# CALclock-r1.net
KiCad netlist of a schematic drawn in EAGLE
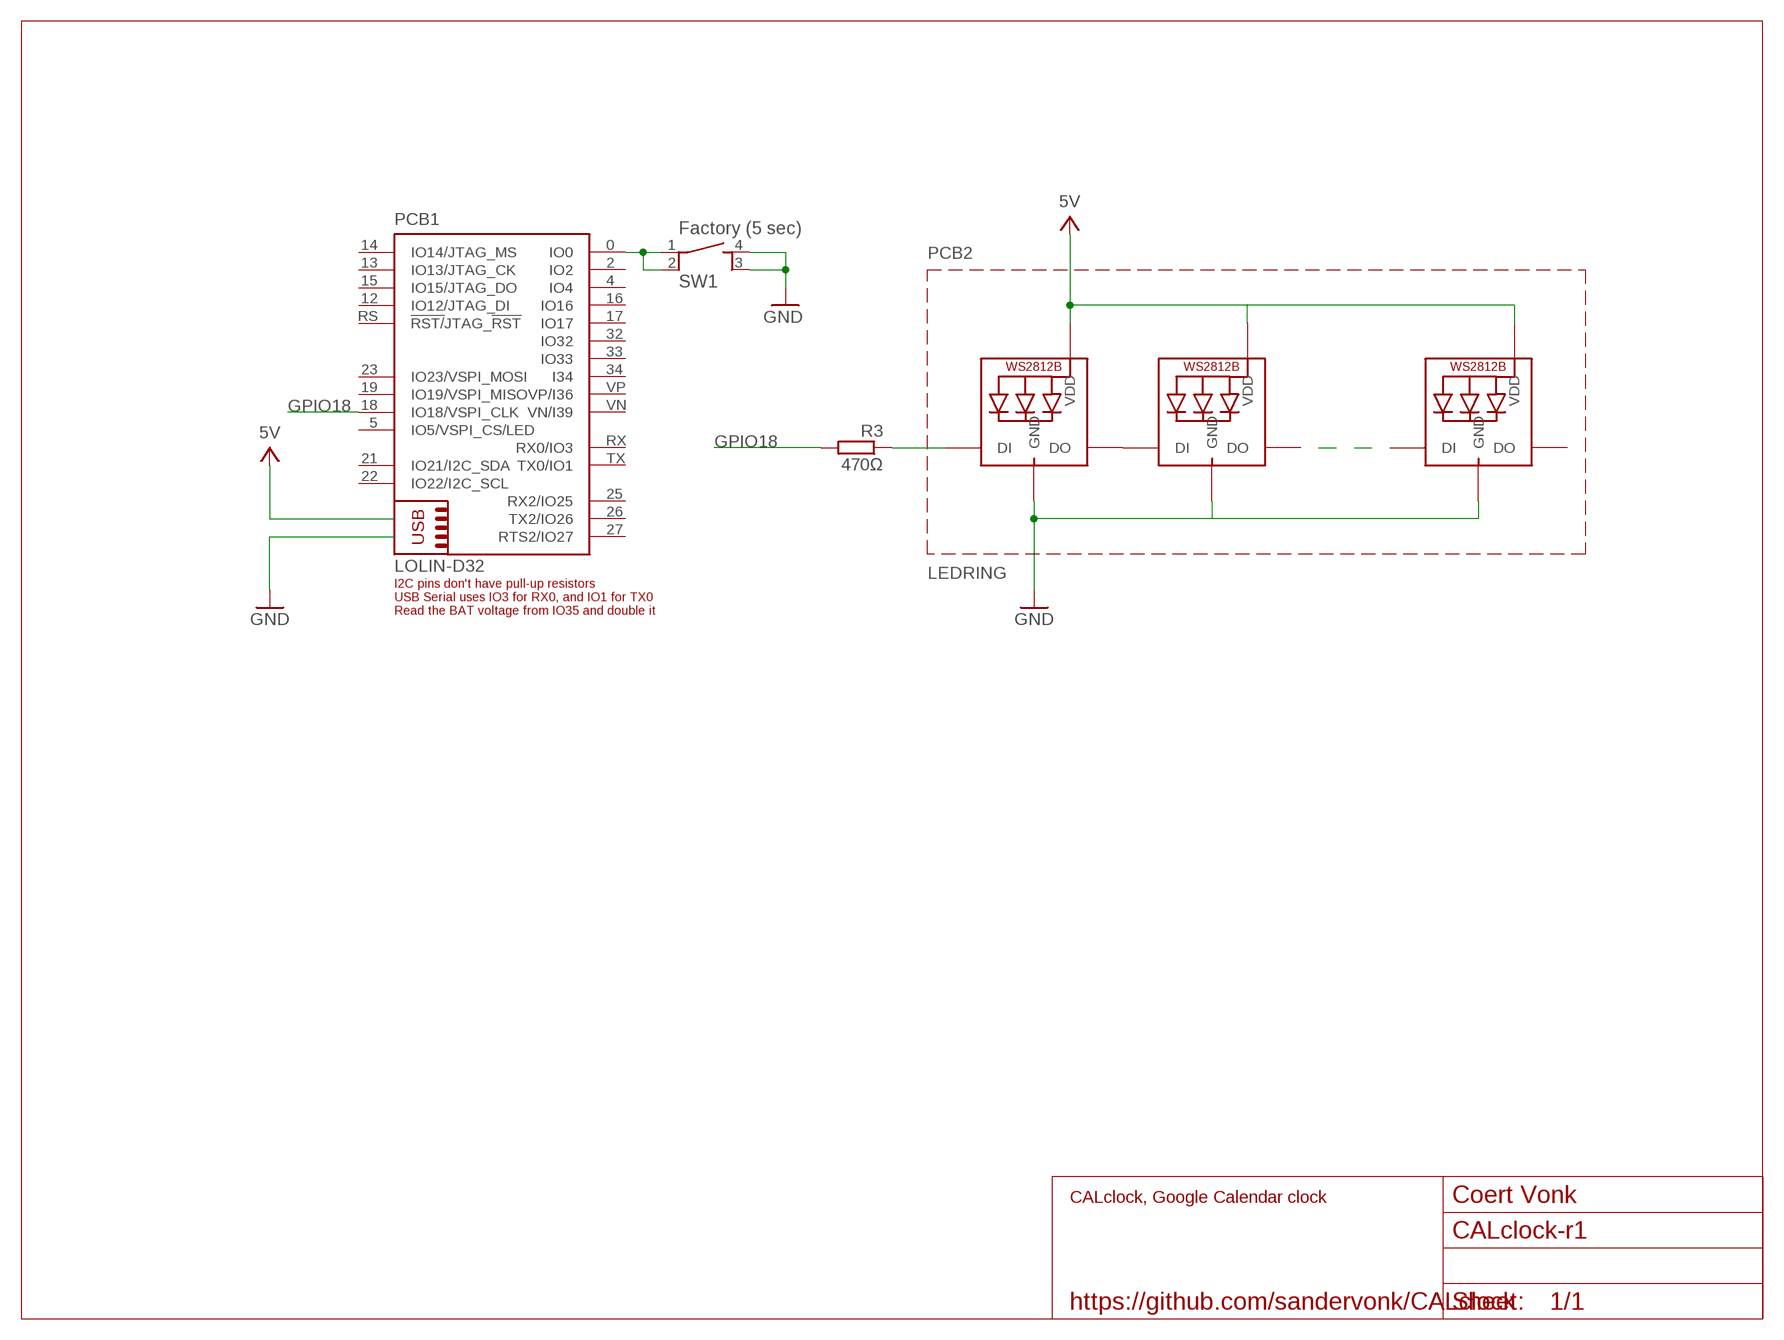
[diagram p0: schematic, sheet 1]

(export (version "E")
  (design (tool "Eeschema 10.0.6"))
  (components
    (comp (ref "LED1")
      (value "WS2812B5050")
      (footprint "eagle-import:WS2812B")
      (fields (field (name "MF") "Seeed Technology") (field (name "MP") "WS2812B"))
      (libsource (lib "eagle-import") (part "WS2812B5050"))
    )
    (comp (ref "LED2")
      (value "WS2812B5050")
      (footprint "eagle-import:WS2812B")
      (fields (field (name "MF") "Seeed Technology") (field (name "MP") "WS2812B"))
      (libsource (lib "eagle-import") (part "WS2812B5050"))
    )
    (comp (ref "LED3")
      (value "WS2812B5050")
      (footprint "eagle-import:WS2812B")
      (fields (field (name "MF") "Seeed Technology") (field (name "MP") "WS2812B"))
      (libsource (lib "eagle-import") (part "WS2812B5050"))
    )
    (comp (ref "PCB1")
      (value "LOLIN-D32")
      (footprint "eagle-import:LOLIN-D32")
      (fields (field (name "MANF") "WEMOS Electronics"))
      (libsource (lib "eagle-import") (part "LOLIN-D32"))
    )
    (comp (ref "R3")
      (value "470Ω")
      (footprint "eagle-import:R0805")
      (fields (field (name "MANF") "Bourns"))
      (libsource (lib "eagle-import") (part "R-EU_R0805"))
    )
    (comp (ref "SW1")
      (value "Factory (5 sec)")
      (footprint "eagle-import:TE_1-1825910-4")
      (fields
        (field (name "COMMENT") "1-1825910-4")
        (field (name "DIGI-KEY_PART_NUMBER") "450-1653-ND")
        (field (name "MF") "TE Connectivity")
      )
      (libsource (lib "eagle-import") (part "1-1825910-4"))
    )
  )
  (nets
    (net (code "1") (name "/GPIO18") (class "Default")
      (node (ref "PCB1") (pin "18") (pinfunction "IO18/VSPI_CLK_18") (pintype "bidirectional"))
      (node (ref "R3") (pin "2") (pinfunction "2_2") (pintype "passive"))
    )
    (net (code "2") (name "5V") (class "Default")
      (node (ref "LED1") (pin "1-VDD") (pinfunction "VDD_1-VDD") (pintype "power_in"))
      (node (ref "LED3") (pin "1-VDD") (pinfunction "VDD_1-VDD") (pintype "power_in"))
    )
    (net (code "3") (name "GND") (class "Default")
      (node (ref "LED1") (pin "3-GND") (pinfunction "GND_3-GND") (pintype "power_in"))
      (node (ref "LED3") (pin "3-GND") (pinfunction "GND_3-GND") (pintype "power_in"))
      (node (ref "SW1") (pin "3") (pinfunction "3_3") (pintype "passive"))
      (node (ref "SW1") (pin "4") (pinfunction "4_4") (pintype "passive"))
    )
    (net (code "4") (name "Net-(LED1-DI)") (class "Default")
      (node (ref "LED1") (pin "4-DIN") (pinfunction "DI_4-DIN") (pintype "input"))
      (node (ref "R3") (pin "1") (pinfunction "1_1") (pintype "passive"))
    )
    (net (code "5") (name "Net-(LED1-DO)") (class "Default")
      (node (ref "LED1") (pin "2-DOUT") (pinfunction "DO_2-DOUT") (pintype "output"))
      (node (ref "LED2") (pin "4-DIN") (pinfunction "DI_4-DIN") (pintype "input"))
    )
    (net (code "6") (name "Net-(PCB1A-IO0)") (class "Default")
      (node (ref "PCB1") (pin "0") (pinfunction "IO0_0") (pintype "bidirectional"))
      (node (ref "SW1") (pin "1") (pinfunction "1_1") (pintype "passive"))
      (node (ref "SW1") (pin "2") (pinfunction "2_2") (pintype "passive"))
    )
    (net (code "7") (name "unconnected-(LED2-DO-Pad2-DOUT)") (class "Default")
      (node (ref "LED2") (pin "2-DOUT") (pinfunction "DO_2-DOUT") (pintype "output"))
    )
    (net (code "8") (name "unconnected-(LED2-GND-Pad3-GND)") (class "Default")
      (node (ref "LED2") (pin "3-GND") (pinfunction "GND_3-GND") (pintype "power_in"))
    )
    (net (code "9") (name "unconnected-(LED2-VDD-Pad1-VDD)") (class "Default")
      (node (ref "LED2") (pin "1-VDD") (pinfunction "VDD_1-VDD") (pintype "power_in"))
    )
    (net (code "10") (name "unconnected-(LED3-DI-Pad4-DIN)") (class "Default")
      (node (ref "LED3") (pin "4-DIN") (pinfunction "DI_4-DIN") (pintype "input"))
    )
    (net (code "11") (name "unconnected-(LED3-DO-Pad2-DOUT)") (class "Default")
      (node (ref "LED3") (pin "2-DOUT") (pinfunction "DO_2-DOUT") (pintype "output"))
    )
    (net (code "12") (name "unconnected-(PCB1A-I34-Pad34)") (class "Default")
      (node (ref "PCB1") (pin "34") (pinfunction "I34_34") (pintype "input"))
    )
    (net (code "13") (name "unconnected-(PCB1A-IO2-Pad2)") (class "Default")
      (node (ref "PCB1") (pin "2") (pinfunction "IO2_2") (pintype "bidirectional"))
    )
    (net (code "14") (name "unconnected-(PCB1A-IO4-Pad4)") (class "Default")
      (node (ref "PCB1") (pin "4") (pinfunction "IO4_4") (pintype "bidirectional"))
    )
    (net (code "15") (name "unconnected-(PCB1A-IO5{slash}VSPI_CS{slash}LED-Pad5)") (class "Default")
      (node (ref "PCB1") (pin "5") (pinfunction "IO5/VSPI_CS/LED_5") (pintype "bidirectional"))
    )
    (net (code "16") (name "unconnected-(PCB1A-IO12{slash}JTAG_DI-Pad12)") (class "Default")
      (node (ref "PCB1") (pin "12") (pinfunction "IO12/JTAG_DI_12") (pintype "bidirectional"))
    )
    (net (code "17") (name "unconnected-(PCB1A-IO13{slash}JTAG_CK-Pad13)") (class "Default")
      (node (ref "PCB1") (pin "13") (pinfunction "IO13/JTAG_CK_13") (pintype "bidirectional"))
    )
    (net (code "18") (name "unconnected-(PCB1A-IO14{slash}JTAG_MS-Pad14)") (class "Default")
      (node (ref "PCB1") (pin "14") (pinfunction "IO14/JTAG_MS_14") (pintype "bidirectional"))
    )
    (net (code "19") (name "unconnected-(PCB1A-IO15{slash}JTAG_DO-Pad15)") (class "Default")
      (node (ref "PCB1") (pin "15") (pinfunction "IO15/JTAG_DO_15") (pintype "bidirectional"))
    )
    (net (code "20") (name "unconnected-(PCB1A-IO16-Pad16)") (class "Default")
      (node (ref "PCB1") (pin "16") (pinfunction "IO16_16") (pintype "bidirectional"))
    )
    (net (code "21") (name "unconnected-(PCB1A-IO17-Pad17)") (class "Default")
      (node (ref "PCB1") (pin "17") (pinfunction "IO17_17") (pintype "bidirectional"))
    )
    (net (code "22") (name "unconnected-(PCB1A-IO19{slash}VSPI_MISO-Pad19)") (class "Default")
      (node (ref "PCB1") (pin "19") (pinfunction "IO19/VSPI_MISO_19") (pintype "bidirectional"))
    )
    (net (code "23") (name "unconnected-(PCB1A-IO21{slash}I2C_SDA-Pad21)") (class "Default")
      (node (ref "PCB1") (pin "21") (pinfunction "IO21/I2C_SDA_21") (pintype "bidirectional"))
    )
    (net (code "24") (name "unconnected-(PCB1A-IO22{slash}I2C_SCL-Pad22)") (class "Default")
      (node (ref "PCB1") (pin "22") (pinfunction "IO22/I2C_SCL_22") (pintype "bidirectional"))
    )
    (net (code "25") (name "unconnected-(PCB1A-IO23{slash}VSPI_MOSI-Pad23)") (class "Default")
      (node (ref "PCB1") (pin "23") (pinfunction "IO23/VSPI_MOSI_23") (pintype "bidirectional"))
    )
    (net (code "26") (name "unconnected-(PCB1A-IO32-Pad32)") (class "Default")
      (node (ref "PCB1") (pin "32") (pinfunction "IO32_32") (pintype "bidirectional"))
    )
    (net (code "27") (name "unconnected-(PCB1A-IO33-Pad33)") (class "Default")
      (node (ref "PCB1") (pin "33") (pinfunction "IO33_33") (pintype "bidirectional"))
    )
    (net (code "28") (name "unconnected-(PCB1A-RTS2{slash}IO27-Pad27)") (class "Default")
      (node (ref "PCB1") (pin "27") (pinfunction "RTS2/IO27_27") (pintype "bidirectional"))
    )
    (net (code "29") (name "unconnected-(PCB1A-RX0{slash}IO3-PadRX)") (class "Default")
      (node (ref "PCB1") (pin "RX") (pinfunction "RX0/IO3_RX") (pintype "bidirectional"))
    )
    (net (code "30") (name "unconnected-(PCB1A-RX2{slash}IO25-Pad25)") (class "Default")
      (node (ref "PCB1") (pin "25") (pinfunction "RX2/IO25_25") (pintype "bidirectional"))
    )
    (net (code "31") (name "unconnected-(PCB1A-TX0{slash}IO1-PadTX)") (class "Default")
      (node (ref "PCB1") (pin "TX") (pinfunction "TX0/IO1_TX") (pintype "bidirectional"))
    )
    (net (code "32") (name "unconnected-(PCB1A-TX2{slash}IO26-Pad26)") (class "Default")
      (node (ref "PCB1") (pin "26") (pinfunction "TX2/IO26_26") (pintype "bidirectional"))
    )
    (net (code "33") (name "unconnected-(PCB1A-VN{slash}I39-PadVN)") (class "Default")
      (node (ref "PCB1") (pin "VN") (pinfunction "VN/I39_VN") (pintype "input"))
    )
    (net (code "34") (name "unconnected-(PCB1A-VP{slash}I36-PadVP)") (class "Default")
      (node (ref "PCB1") (pin "VP") (pinfunction "VP/I36_VP") (pintype "input"))
    )
    (net (code "35") (name "unconnected-(PCB1A-~{RST{slash}}JTAG_~{RST}-PadRS)") (class "Default")
      (node (ref "PCB1") (pin "RS") (pinfunction "~{RST/}JTAG_~{RST}_RS") (pintype "input"))
    )
  )
)
